# oscillator_reannotated.net
KiCad netlist of a schematic drawn in Altium Designer
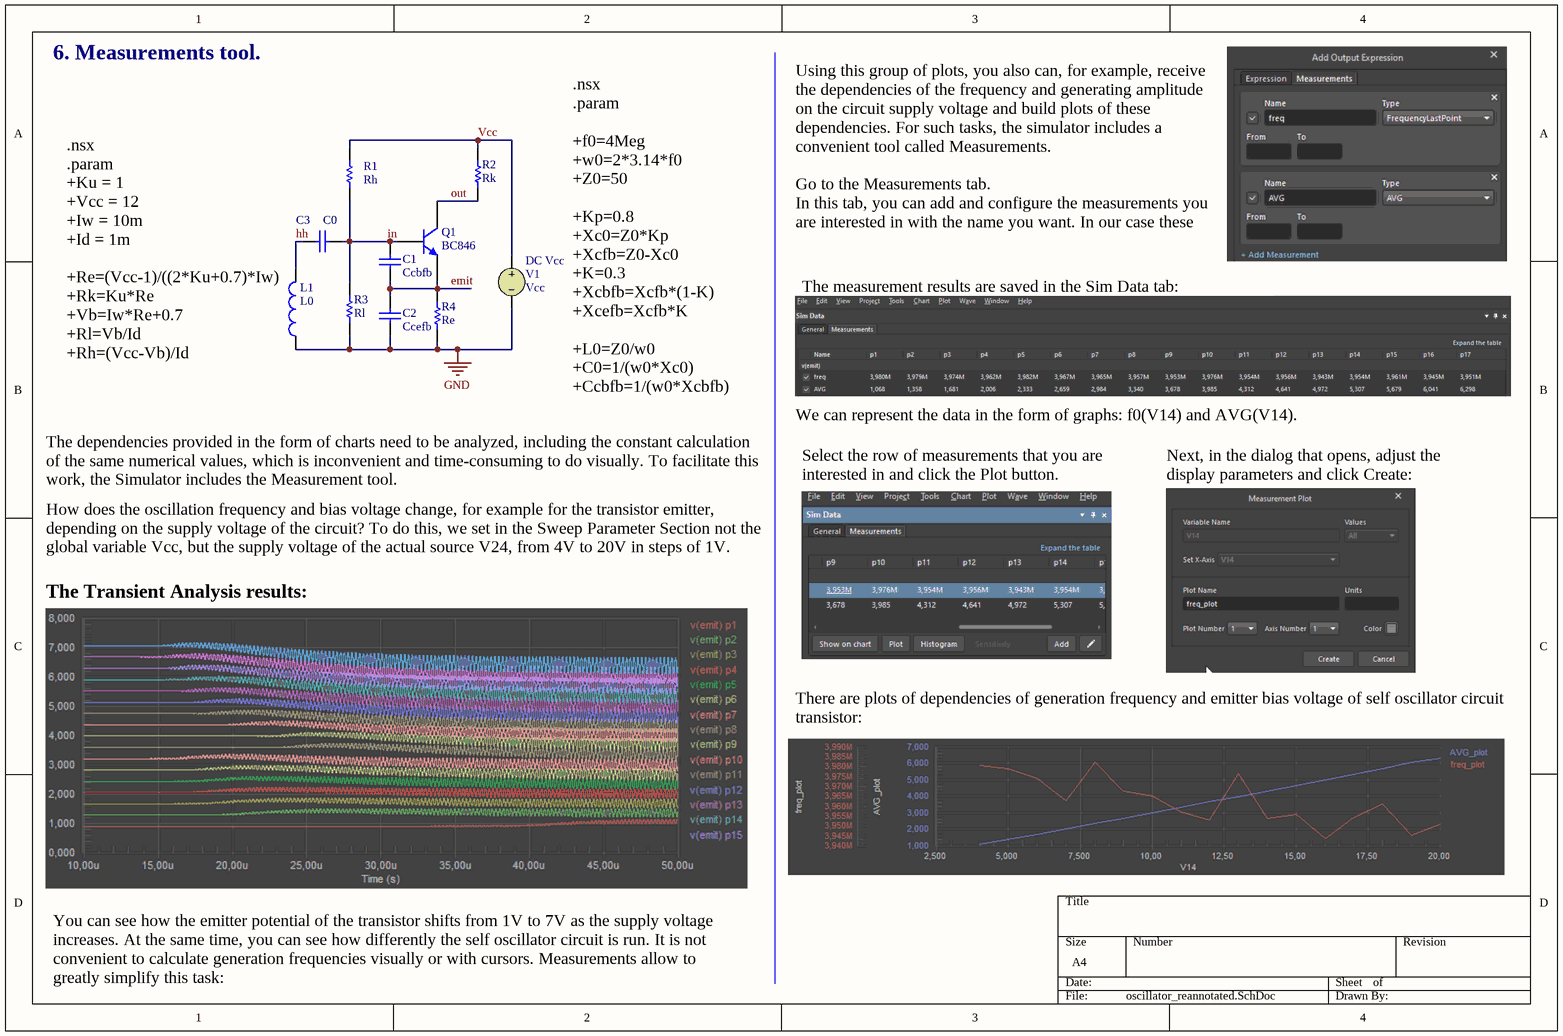
[diagram p0: oscillator_reannotated.SchDoc]

(export (version "E")
  (design (tool "Eeschema 10.0.6"))
  (components
    (comp (ref "C1")
      (value "Ccbfb")
      (description "Capacitor")
      (libsource (lib "Simulation Generic Components") (part "Capacitor"))
    )
    (comp (ref "C2")
      (value "Ccefb")
      (description "Capacitor")
      (libsource (lib "Simulation Generic Components") (part "Capacitor"))
    )
    (comp (ref "C3")
      (value "C0")
      (description "Capacitor")
      (libsource (lib "Simulation Generic Components") (part "Capacitor"))
    )
    (comp (ref "L1")
      (value "L0")
      (description "Inductor")
      (libsource (lib "Simulation Generic Components") (part "Inductor"))
    )
    (comp (ref "Q1")
      (value "BC846")
      (footprint "TO-92A")
      (description "NPN General Purpose Amplifier")
      (fields (field (name "PUBLISHER") "Altium Limited"))
      (libsource (lib "Miscellaneous Devices") (part "2N3904"))
    )
    (comp (ref "R1")
      (value "Rh")
      (description "Resistor")
      (libsource (lib "Simulation Generic Components") (part "Resistor"))
    )
    (comp (ref "R2")
      (value "Rk")
      (description "Resistor")
      (libsource (lib "Simulation Generic Components") (part "Resistor"))
    )
    (comp (ref "R3")
      (value "Rl")
      (description "Resistor")
      (libsource (lib "Simulation Generic Components") (part "Resistor"))
    )
    (comp (ref "R4")
      (value "Re")
      (description "Resistor")
      (libsource (lib "Simulation Generic Components") (part "Resistor"))
    )
    (comp (ref "V1")
      (value "DC Vcc")
      (description "Voltage Source")
      (fields (field (name "ALTIUM_VALUE") "Vcc") (field (name "PUBLISHER") "Altium Limited"))
      (libsource (lib "Simulation Generic Components") (part "VSRC"))
    )
  )
  (nets
    (net (code "1") (name "/Vcc") (class "Default")
      (node (ref "R1") (pin "2") (pinfunction "2_2") (pintype "passive"))
      (node (ref "R2") (pin "2") (pinfunction "2_2") (pintype "passive"))
      (node (ref "V1") (pin "1") (pinfunction "1_1") (pintype "passive"))
    )
    (net (code "2") (name "/emit") (class "Default")
      (node (ref "C1") (pin "1") (pinfunction "1_1") (pintype "passive"))
      (node (ref "C2") (pin "2") (pinfunction "2_2") (pintype "passive"))
      (node (ref "Q1") (pin "1") (pinfunction "E_1") (pintype "passive"))
      (node (ref "R4") (pin "2") (pinfunction "2_2") (pintype "passive"))
    )
    (net (code "3") (name "/hh") (class "Default")
      (node (ref "C3") (pin "1") (pinfunction "1_1") (pintype "passive"))
      (node (ref "L1") (pin "2") (pinfunction "2_2") (pintype "passive"))
    )
    (net (code "4") (name "/in") (class "Default")
      (node (ref "C1") (pin "2") (pinfunction "2_2") (pintype "passive"))
      (node (ref "C3") (pin "2") (pinfunction "2_2") (pintype "passive"))
      (node (ref "Q1") (pin "2") (pinfunction "B_2") (pintype "passive"))
      (node (ref "R1") (pin "1") (pinfunction "1_1") (pintype "passive"))
      (node (ref "R3") (pin "1") (pinfunction "1_1") (pintype "passive"))
    )
    (net (code "5") (name "/out") (class "Default")
      (node (ref "Q1") (pin "3") (pinfunction "C_3") (pintype "passive"))
      (node (ref "R2") (pin "1") (pinfunction "1_1") (pintype "passive"))
    )
    (net (code "6") (name "GND") (class "Default")
      (node (ref "C2") (pin "1") (pinfunction "1_1") (pintype "passive"))
      (node (ref "L1") (pin "1") (pinfunction "1_1") (pintype "passive"))
      (node (ref "R3") (pin "2") (pinfunction "2_2") (pintype "passive"))
      (node (ref "R4") (pin "1") (pinfunction "1_1") (pintype "passive"))
      (node (ref "V1") (pin "2") (pinfunction "2_2") (pintype "passive"))
    )
  )
)
